# power.net
KiCad netlist of a schematic drawn in EAGLE
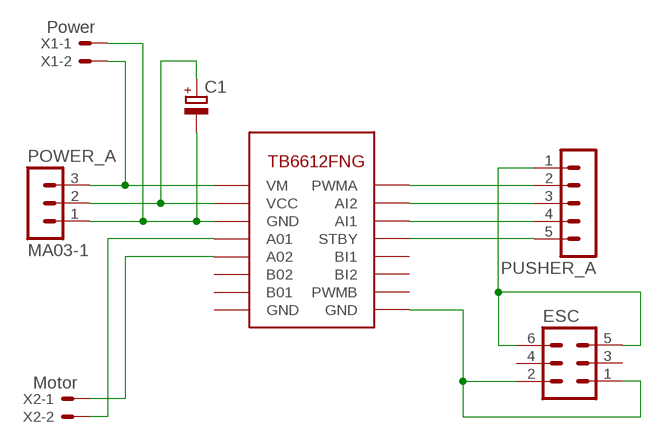
[diagram p0: schematic, sheet 1]

(export (version "E")
  (design (tool "Eeschema 10.0.6"))
  (components
    (comp (ref "C1")
      (value "CPOL-EUTT5D7")
      (footprint "eagle-import:TT5D7")
      (libsource (lib "eagle-import") (part "CPOL-EUTT5D7"))
    )
    (comp (ref "ESC")
      (value "MA03-2")
      (footprint "eagle-import:MA03-2")
      (libsource (lib "eagle-import") (part "MA03-2"))
    )
    (comp (ref "POWER_A")
      (value "MA03-1")
      (footprint "eagle-import:MA03-1")
      (libsource (lib "eagle-import") (part "MA03-1"))
    )
    (comp (ref "PUSHER_A")
      (value "MA05-1")
      (footprint "eagle-import:MA05-1")
      (libsource (lib "eagle-import") (part "MA05-1"))
    )
    (comp (ref "U$2")
      (value "TB6612FNG")
      (footprint "eagle-import:TB6612FNG")
      (libsource (lib "eagle-import") (part "TB6612FNG"))
    )
    (comp (ref "X1")
      (value "Power")
      (footprint "eagle-import:JST-XH-02-PACKAGE-ROUND-PAD")
      (libsource (lib "eagle-import") (part "JST-XH-02-PIN-ROUND-PAD"))
    )
    (comp (ref "X2")
      (value "Motor")
      (footprint "eagle-import:JST-XH-02-PACKAGE-ROUND-PAD")
      (libsource (lib "eagle-import") (part "JST-XH-02-PIN-ROUND-PAD"))
    )
  )
  (nets
    (net (code "1") (name "Net-(ESC-Pad1)") (class "Default")
      (node (ref "ESC") (pin "1") (pinfunction "1_1") (pintype "passive"))
      (node (ref "ESC") (pin "2") (pinfunction "2_2") (pintype "passive"))
      (node (ref "U$2") (pin "P$9") (pinfunction "GND_P$9") (pintype "bidirectional"))
    )
    (net (code "2") (name "Net-(ESC-Pad5)") (class "Default")
      (node (ref "ESC") (pin "5") (pinfunction "5_5") (pintype "passive"))
      (node (ref "ESC") (pin "6") (pinfunction "6_6") (pintype "passive"))
      (node (ref "PUSHER_A") (pin "1") (pinfunction "1_1") (pintype "passive"))
    )
    (net (code "3") (name "Net-(U$2-A01)") (class "Default")
      (node (ref "U$2") (pin "P$4") (pinfunction "A01_P$4") (pintype "bidirectional"))
      (node (ref "X2") (pin "2") (pinfunction "S_2") (pintype "passive"))
    )
    (net (code "4") (name "Net-(U$2-A02)") (class "Default")
      (node (ref "U$2") (pin "P$5") (pinfunction "A02_P$5") (pintype "bidirectional"))
      (node (ref "X2") (pin "1") (pinfunction "S_1") (pintype "passive"))
    )
    (net (code "5") (name "Net-(U$2-AI1)") (class "Default")
      (node (ref "PUSHER_A") (pin "4") (pinfunction "4_4") (pintype "passive"))
      (node (ref "U$2") (pin "P$14") (pinfunction "AI1_P$14") (pintype "bidirectional"))
    )
    (net (code "6") (name "Net-(U$2-AI2)") (class "Default")
      (node (ref "PUSHER_A") (pin "3") (pinfunction "3_3") (pintype "passive"))
      (node (ref "U$2") (pin "P$15") (pinfunction "AI2_P$15") (pintype "bidirectional"))
    )
    (net (code "7") (name "Net-(U$2-PWMA)") (class "Default")
      (node (ref "PUSHER_A") (pin "2") (pinfunction "2_2") (pintype "passive"))
      (node (ref "U$2") (pin "P$16") (pinfunction "PWMA_P$16") (pintype "bidirectional"))
    )
    (net (code "8") (name "Net-(U$2-STBY)") (class "Default")
      (node (ref "PUSHER_A") (pin "5") (pinfunction "5_5") (pintype "passive"))
      (node (ref "U$2") (pin "P$13") (pinfunction "STBY_P$13") (pintype "bidirectional"))
    )
    (net (code "9") (name "Net-(U$2-VCC)") (class "Default")
      (node (ref "C1") (pin "+") (pinfunction "+_+") (pintype "passive"))
      (node (ref "POWER_A") (pin "2") (pinfunction "2_2") (pintype "passive"))
      (node (ref "U$2") (pin "P$2") (pinfunction "VCC_P$2") (pintype "bidirectional"))
    )
    (net (code "10") (name "Net-(U$2-VM)") (class "Default")
      (node (ref "POWER_A") (pin "3") (pinfunction "3_3") (pintype "passive"))
      (node (ref "U$2") (pin "P$1") (pinfunction "VM_P$1") (pintype "bidirectional"))
      (node (ref "X1") (pin "2") (pinfunction "S_2") (pintype "passive"))
    )
    (net (code "11") (name "Net-(X1A-S)") (class "Default")
      (node (ref "C1") (pin "-") (pinfunction "-_-") (pintype "passive"))
      (node (ref "POWER_A") (pin "1") (pinfunction "1_1") (pintype "passive"))
      (node (ref "U$2") (pin "P$3") (pinfunction "GND_P$3") (pintype "bidirectional"))
      (node (ref "X1") (pin "1") (pinfunction "S_1") (pintype "passive"))
    )
    (net (code "12") (name "unconnected-(ESC-Pad3)") (class "Default")
      (node (ref "ESC") (pin "3") (pinfunction "3_3") (pintype "passive"))
    )
    (net (code "13") (name "unconnected-(ESC-Pad4)") (class "Default")
      (node (ref "ESC") (pin "4") (pinfunction "4_4") (pintype "passive"))
    )
    (net (code "14") (name "unconnected-(U$2-B01-PadP$7)") (class "Default")
      (node (ref "U$2") (pin "P$7") (pinfunction "B01_P$7") (pintype "bidirectional"))
    )
    (net (code "15") (name "unconnected-(U$2-B02-PadP$6)") (class "Default")
      (node (ref "U$2") (pin "P$6") (pinfunction "B02_P$6") (pintype "bidirectional"))
    )
    (net (code "16") (name "unconnected-(U$2-BI1-PadP$12)") (class "Default")
      (node (ref "U$2") (pin "P$12") (pinfunction "BI1_P$12") (pintype "bidirectional"))
    )
    (net (code "17") (name "unconnected-(U$2-BI2-PadP$11)") (class "Default")
      (node (ref "U$2") (pin "P$11") (pinfunction "BI2_P$11") (pintype "bidirectional"))
    )
    (net (code "18") (name "unconnected-(U$2-GND-PadP$8)") (class "Default")
      (node (ref "U$2") (pin "P$8") (pinfunction "GND_P$8") (pintype "bidirectional"))
    )
    (net (code "19") (name "unconnected-(U$2-PWMB-PadP$10)") (class "Default")
      (node (ref "U$2") (pin "P$10") (pinfunction "PWMB_P$10") (pintype "bidirectional"))
    )
  )
)
